# QCopterMV_KEY_Sch.net
KiCad netlist of a schematic drawn in Altium Designer
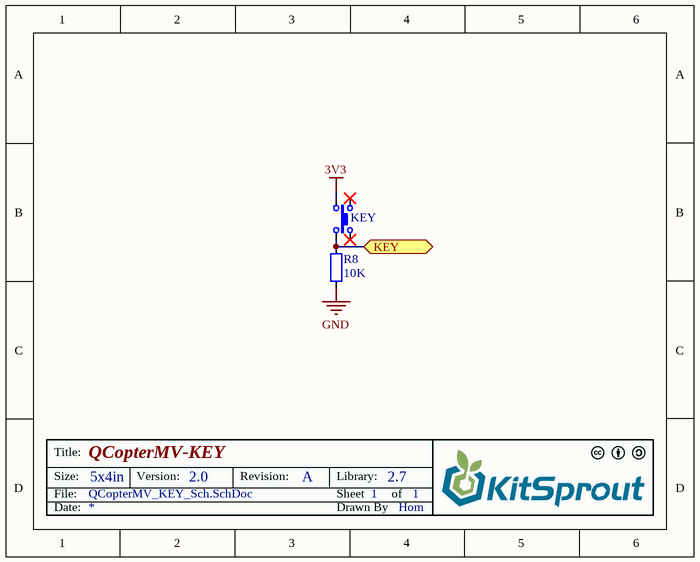
[diagram p0: QCopterMV_KEY_Sch.SchDoc]

(export (version "E")
  (design (tool "Eeschema 10.0.6"))
  (components
    (comp (ref "KEY")
      (value "ButtonTACT")
      (footprint "PCB_Switch:ButtonTACT_3.5*3.55_90")
      (description "Button")
      (libsource (lib "SCH_Switch") (part "ButtonTACT"))
    )
    (comp (ref "R8")
      (value "10K")
      (footprint "PCB_PassiveRes:RES_0603")
      (description "Resistor")
      (fields (field (name "Comment") "Res_0603"))
      (libsource (lib "SCH_Passive") (part "Res_0603"))
    )
  )
  (nets
    (net (code "1") (name "/KEY") (class "Default")
      (node (ref "KEY") (pin "4") (pinfunction "4_4") (pintype "passive"))
      (node (ref "R8") (pin "2") (pinfunction "2_2") (pintype "passive"))
    )
    (net (code "2") (name "3V3") (class "Default")
      (node (ref "KEY") (pin "3") (pinfunction "3_3") (pintype "passive"))
    )
    (net (code "3") (name "GND") (class "Default")
      (node (ref "R8") (pin "1") (pinfunction "1_1") (pintype "passive"))
    )
    (net (code "4") (name "unconnected-(KEY-Pad1)") (class "Default")
      (node (ref "KEY") (pin "1") (pinfunction "1_1") (pintype "passive+no_connect"))
    )
    (net (code "5") (name "unconnected-(KEY-Pad2)") (class "Default")
      (node (ref "KEY") (pin "2") (pinfunction "2_2") (pintype "passive+no_connect"))
    )
  )
)
